# Mainboard_RMII_Interface.net
KiCad netlist of a schematic drawn in Altium Designer
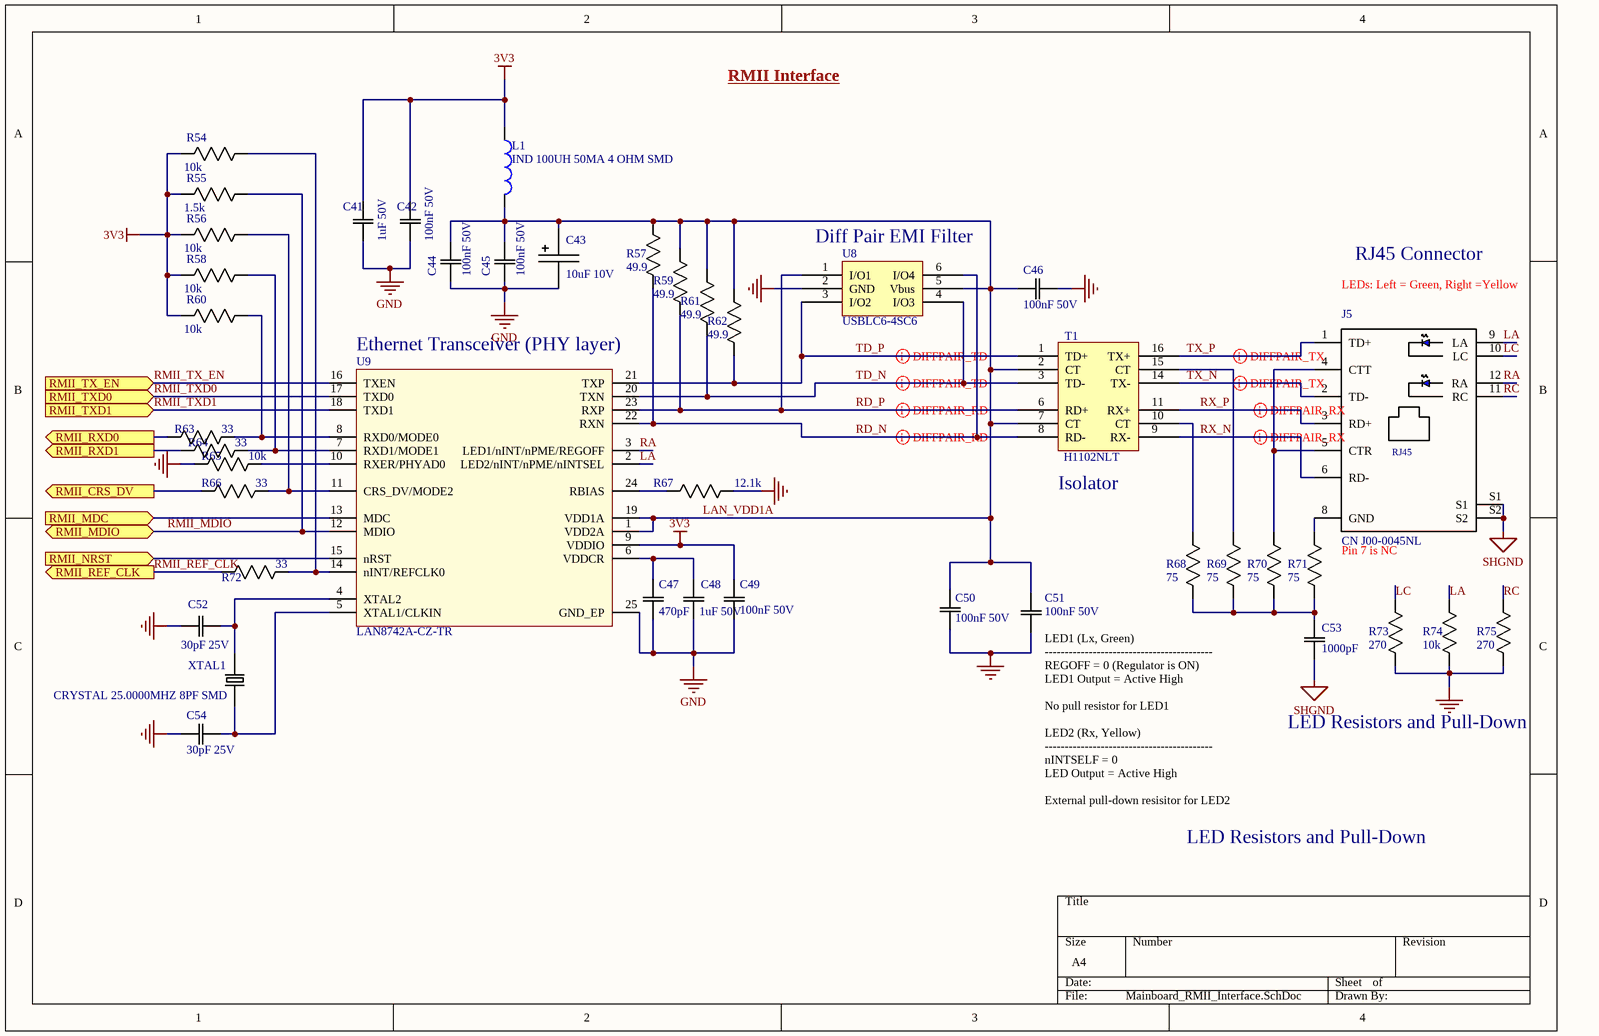
[diagram p0: Mainboard_RMII_Interface.SchDoc]

(export (version "E")
  (design (tool "Eeschema 10.0.6"))
  (components
    (comp (ref "C41")
      (value "1uF 50V")
      (footprint "0805")
      (description "CAP CER 1UF 50V X7R 0805")
      (fields (field (name "TOLERANCE") "10%"))
      (libsource (lib "AltiumLibraries") (part "CAP 1uF 50V"))
    )
    (comp (ref "C42")
      (value "100nF 50V")
      (footprint "0805")
      (description "CAP CER 0.1UF 50V X7R 0805")
      (fields (field (name "TOLERANCE") "10%"))
      (libsource (lib "AltiumLibraries") (part "CAP 100nF 50V"))
    )
    (comp (ref "C43")
      (value "10uF 10V")
      (footprint "1206 Polarized")
      (description "CAP TANT 10UF 10V 1206")
      (fields (field (name "TOLERANCE") "10%"))
      (libsource (lib "AltiumLibraries") (part "CAP TANT 10uF 10V"))
    )
    (comp (ref "C44")
      (value "100nF 50V")
      (footprint "0805")
      (description "CAP CER 0.1UF 50V X7R 0805")
      (fields (field (name "TOLERANCE") "10%"))
      (libsource (lib "AltiumLibraries") (part "CAP 100nF 50V"))
    )
    (comp (ref "C45")
      (value "100nF 50V")
      (footprint "0805")
      (description "CAP CER 0.1UF 50V X7R 0805")
      (fields (field (name "TOLERANCE") "10%"))
      (libsource (lib "AltiumLibraries") (part "CAP 100nF 50V"))
    )
    (comp (ref "C46")
      (value "100nF 50V")
      (footprint "0805")
      (description "CAP CER 0.1UF 50V X7R 0805")
      (fields (field (name "TOLERANCE") "10%"))
      (libsource (lib "AltiumLibraries") (part "CAP 100nF 50V"))
    )
    (comp (ref "C47")
      (value "470pF")
      (footprint "0805")
      (description "CAP CER 470PF 50V X7R 0603/0805")
      (fields (field (name "TOLERANCE") "10%"))
      (libsource (lib "AltiumLibraries") (part "CAP 470pF 50V"))
    )
    (comp (ref "C48")
      (value "1uF 50V")
      (footprint "0805")
      (description "CAP CER 1UF 50V X7R 0805")
      (fields (field (name "TOLERANCE") "10%"))
      (libsource (lib "AltiumLibraries") (part "CAP 1uF 50V"))
    )
    (comp (ref "C49")
      (value "100nF 50V")
      (footprint "0805")
      (description "CAP CER 0.1UF 50V X7R 0805")
      (fields (field (name "TOLERANCE") "10%"))
      (libsource (lib "AltiumLibraries") (part "CAP 100nF 50V"))
    )
    (comp (ref "C50")
      (value "100nF 50V")
      (footprint "0805")
      (description "CAP CER 0.1UF 50V X7R 0805")
      (fields (field (name "TOLERANCE") "10%"))
      (libsource (lib "AltiumLibraries") (part "CAP 100nF 50V"))
    )
    (comp (ref "C51")
      (value "100nF 50V")
      (footprint "0805")
      (description "CAP CER 0.1UF 50V X7R 0805")
      (fields (field (name "TOLERANCE") "10%"))
      (libsource (lib "AltiumLibraries") (part "CAP 100nF 50V"))
    )
    (comp (ref "C52")
      (value "30pF 25V")
      (footprint "0805")
      (description "CAP CER 30PF 25V NP0 0805")
      (fields (field (name "TOLERANCE") "20%"))
      (libsource (lib "AltiumLibraries") (part "CAP 30pF 25V"))
    )
    (comp (ref "C53")
      (value "1000pF")
      (footprint "0805")
      (description "CAP CER 1000PF 50V X7R 0603/0805")
      (fields (field (name "TOLERANCE") "10%"))
      (libsource (lib "AltiumLibraries") (part "CAP 1000pF 50V"))
    )
    (comp (ref "C54")
      (value "30pF 25V")
      (footprint "0805")
      (description "CAP CER 30PF 25V NP0 0805")
      (fields (field (name "TOLERANCE") "20%"))
      (libsource (lib "AltiumLibraries") (part "CAP 30pF 25V"))
    )
    (comp (ref "J5")
      (value "CN J00-0045NL")
      (footprint "RJ45 J00-0045NL")
      (description "CN MAGJACK 1PORT 100 BASE-TX")
      (fields (field (name "MF") "Pulse Electronics") (field (name "MP") "J00-0045NL"))
      (libsource (lib "AltiumLibraries") (part "CN MAGJACK"))
    )
    (comp (ref "L1")
      (value "IND 100UH 50MA 4 OHM SMD")
      (footprint "0805")
      (description "100µH Unshielded Wirewound Inductor 50mA 4Ohm 0805 (2012 Metric)")
      (fields (field (name "MF") "Taiyo Yuden") (field (name "MP") "LBR2012T101K"))
      (libsource (lib "AltiumLibraries") (part "IND 100UH 50MA 4 OHM SMD"))
    )
    (comp (ref "R54")
      (value "10k")
      (footprint "0805")
      (description "RES SMD 10K OHM 1% 1/8W 0805")
      (fields (field (name "TOLERANCE") "1%"))
      (libsource (lib "") (part "RES 10k 1/8W - 1%_1"))
    )
    (comp (ref "R55")
      (value "1.5k")
      (footprint "0805")
      (description "RES SMD 1.5K OHM 1% 1/8W 0805")
      (fields (field (name "TOLERANCE") "1%"))
      (libsource (lib "AltiumLibraries") (part "RES 1.5k 1/8W - 1%"))
    )
    (comp (ref "R56")
      (value "10k")
      (footprint "0805")
      (description "RES SMD 10K OHM 1% 1/8W 0805")
      (fields (field (name "TOLERANCE") "1%"))
      (libsource (lib "AltiumLibraries") (part "RES 10k 1/8W - 1%"))
    )
    (comp (ref "R57")
      (value "49.9")
      (footprint "0805")
      (description "RES SMD 49.9 OHM 1% 1/8W 0805")
      (fields (field (name "TOLERANCE") "1%"))
      (libsource (lib "AltiumLibraries") (part "RES 49.9 1/8W"))
    )
    (comp (ref "R58")
      (value "10k")
      (footprint "0805")
      (description "RES SMD 10K OHM 1% 1/8W 0805")
      (fields (field (name "TOLERANCE") "1%"))
      (libsource (lib "") (part "RES 10k 1/8W - 1%_1"))
    )
    (comp (ref "R59")
      (value "49.9")
      (footprint "0805")
      (description "RES SMD 49.9 OHM 1% 1/8W 0805")
      (fields (field (name "TOLERANCE") "1%"))
      (libsource (lib "AltiumLibraries") (part "RES 49.9 1/8W"))
    )
    (comp (ref "R60")
      (value "10k")
      (footprint "0805")
      (description "RES SMD 10K OHM 1% 1/8W 0805")
      (fields (field (name "TOLERANCE") "1%"))
      (libsource (lib "") (part "RES 10k 1/8W - 1%_1"))
    )
    (comp (ref "R61")
      (value "49.9")
      (footprint "0805")
      (description "RES SMD 49.9 OHM 1% 1/8W 0805")
      (fields (field (name "TOLERANCE") "1%"))
      (libsource (lib "AltiumLibraries") (part "RES 49.9 1/8W"))
    )
    (comp (ref "R62")
      (value "49.9")
      (footprint "0805")
      (description "RES SMD 49.9 OHM 1% 1/8W 0805")
      (fields (field (name "TOLERANCE") "1%"))
      (libsource (lib "AltiumLibraries") (part "RES 49.9 1/8W"))
    )
    (comp (ref "R63")
      (value "33")
      (footprint "0805")
      (description "RES SMD 33 OHM 1% 1/8W 0805")
      (fields (field (name "TOLERANCE") "1%"))
      (libsource (lib "AltiumLibraries") (part "RES 33.0 1/8W - 1%"))
    )
    (comp (ref "R64")
      (value "33")
      (footprint "0805")
      (description "RES SMD 33 OHM 1% 1/8W 0805")
      (fields (field (name "TOLERANCE") "1%"))
      (libsource (lib "AltiumLibraries") (part "RES 33.0 1/8W - 1%"))
    )
    (comp (ref "R65")
      (value "10k")
      (footprint "0805")
      (description "RES SMD 10K OHM 1% 1/8W 0805")
      (fields (field (name "TOLERANCE") "1%"))
      (libsource (lib "AltiumLibraries") (part "RES 10k 1/8W - 1%"))
    )
    (comp (ref "R66")
      (value "33")
      (footprint "0805")
      (description "RES SMD 33 OHM 1% 1/8W 0805")
      (fields (field (name "TOLERANCE") "1%"))
      (libsource (lib "AltiumLibraries") (part "RES 33.0 1/8W - 1%"))
    )
    (comp (ref "R67")
      (value "12.1k")
      (footprint "0805")
      (description "RES SMD 12.1K OHM 1% 1/8W 0805")
      (fields (field (name "TOLERANCE") "1%"))
      (libsource (lib "AltiumLibraries") (part "RES 12.1k 1/8W"))
    )
    (comp (ref "R68")
      (value "75")
      (footprint "0805")
      (description "RES SMD 75 OHM 1% 1/8W 0805")
      (fields (field (name "TOLERANCE") "1%"))
      (libsource (lib "AltiumLibraries") (part "RES 75.0 1/8W - 1%"))
    )
    (comp (ref "R69")
      (value "75")
      (footprint "0805")
      (description "RES SMD 75 OHM 1% 1/8W 0805")
      (fields (field (name "TOLERANCE") "1%"))
      (libsource (lib "AltiumLibraries") (part "RES 75.0 1/8W - 1%"))
    )
    (comp (ref "R70")
      (value "75")
      (footprint "0805")
      (description "RES SMD 75 OHM 1% 1/8W 0805")
      (fields (field (name "TOLERANCE") "1%"))
      (libsource (lib "AltiumLibraries") (part "RES 75.0 1/8W - 1%"))
    )
    (comp (ref "R71")
      (value "75")
      (footprint "0805")
      (description "RES SMD 75 OHM 1% 1/8W 0805")
      (fields (field (name "TOLERANCE") "1%"))
      (libsource (lib "AltiumLibraries") (part "RES 75.0 1/8W - 1%"))
    )
    (comp (ref "R72")
      (value "33")
      (footprint "0805")
      (description "RES SMD 33 OHM 1% 1/8W 0805")
      (fields (field (name "TOLERANCE") "1%"))
      (libsource (lib "AltiumLibraries") (part "RES 33.0 1/8W - 1%"))
    )
    (comp (ref "R73")
      (value "270")
      (footprint "0805")
      (description "RES SMD 270 OHM 5% 1/8W 0805")
      (fields (field (name "TOLERANCE") "5%"))
      (libsource (lib "AltiumLibraries") (part "RES 270.0 1/8W"))
    )
    (comp (ref "R74")
      (value "10k")
      (footprint "0805")
      (description "RES SMD 10K OHM 1% 1/8W 0805")
      (fields (field (name "TOLERANCE") "1%"))
      (libsource (lib "") (part "RES 10k 1/8W - 1%_1"))
    )
    (comp (ref "R75")
      (value "270")
      (footprint "0805")
      (description "RES SMD 270 OHM 5% 1/8W 0805")
      (fields (field (name "TOLERANCE") "5%"))
      (libsource (lib "AltiumLibraries") (part "RES 270.0 1/8W"))
    )
    (comp (ref "T1")
      (value "H1102NLT")
      (footprint "TRANSFORMER")
      (fields (field (name "MF") "Pulse Electronics") (field (name "MP") "H1102NL"))
      (libsource (lib "AltiumLibraries") (part "XFRMR H1102NLT"))
    )
    (comp (ref "U8")
      (value "USBLC6-4SC6")
      (footprint "SOT23-6L")
      (libsource (lib "AltiumLibraries") (part "USBLC6-4SC6"))
    )
    (comp (ref "U9")
      (value "LAN8742A-CZ-TR")
      (footprint "24-QFN (4x4)")
      (fields (field (name "MF") "Microchip Technology"))
      (libsource (lib "AltiumLibraries") (part "LAN8742A-CZ-TR"))
    )
    (comp (ref "XTAL1")
      (value "CRYSTAL 25.0000MHZ 8PF SMD")
      (footprint "SMD-2")
      (description "25MHz ±50ppm Crystal 8pF 70 Ohms 2-SMD, No Lead")
      (fields (field (name "MP") "NX5032GA-25.000000MHZ-LN-CD-1") (field (name "MF") "NDK America, Inc."))
      (libsource (lib "AltiumLibraries") (part "XTAL 25MHZ 8PF SMD"))
    )
  )
  (nets
    (net (code "1") (name "/LA") (class "Default")
      (node (ref "J5") (pin "9") (pinfunction "LA_9") (pintype "passive"))
      (node (ref "R74") (pin "1") (pinfunction "R1_1") (pintype "passive"))
      (node (ref "U9") (pin "2") (pinfunction "LED2/nINT/nPME/nINTSEL_2") (pintype "passive"))
    )
    (net (code "2") (name "/LAN_VDD1A") (class "Default")
      (node (ref "C43") (pin "1") (pinfunction "P$1_1") (pintype "passive"))
      (node (ref "C44") (pin "2") (pinfunction "C2_2") (pintype "passive"))
      (node (ref "C45") (pin "2") (pinfunction "C2_2") (pintype "passive"))
      (node (ref "C46") (pin "1") (pinfunction "C1_1") (pintype "passive"))
      (node (ref "C50") (pin "2") (pinfunction "C2_2") (pintype "passive"))
      (node (ref "C51") (pin "2") (pinfunction "C2_2") (pintype "passive"))
      (node (ref "L1") (pin "2") (pinfunction "2_2") (pintype "passive"))
      (node (ref "R57") (pin "1") (pinfunction "R1_1") (pintype "passive"))
      (node (ref "R59") (pin "1") (pinfunction "R1_1") (pintype "passive"))
      (node (ref "R61") (pin "1") (pinfunction "R1_1") (pintype "passive"))
      (node (ref "R62") (pin "1") (pinfunction "R1_1") (pintype "passive"))
      (node (ref "T1") (pin "2") (pinfunction "CT_2") (pintype "passive"))
      (node (ref "T1") (pin "7") (pinfunction "CT_7") (pintype "passive"))
      (node (ref "U8") (pin "5") (pinfunction "Vbus_5") (pintype "passive"))
      (node (ref "U9") (pin "1") (pinfunction "VDD2A_1") (pintype "passive"))
      (node (ref "U9") (pin "19") (pinfunction "VDD1A_19") (pintype "passive"))
    )
    (net (code "3") (name "/LC") (class "Default")
      (node (ref "J5") (pin "10") (pinfunction "LC_10") (pintype "passive"))
      (node (ref "R73") (pin "1") (pinfunction "R1_1") (pintype "passive"))
    )
    (net (code "4") (name "/RA") (class "Default")
      (node (ref "J5") (pin "12") (pinfunction "RA_12") (pintype "passive"))
      (node (ref "U9") (pin "3") (pinfunction "LED1/nINT/nPME/REGOFF_3") (pintype "passive"))
    )
    (net (code "5") (name "/RC") (class "Default")
      (node (ref "J5") (pin "11") (pinfunction "RC_11") (pintype "passive"))
      (node (ref "R75") (pin "1") (pinfunction "R1_1") (pintype "passive"))
    )
    (net (code "6") (name "/RD_N") (class "Default")
      (node (ref "R57") (pin "2") (pinfunction "R2_2") (pintype "passive"))
      (node (ref "T1") (pin "8") (pinfunction "RD-_8") (pintype "passive"))
      (node (ref "U8") (pin "6") (pinfunction "I/O4_6") (pintype "passive"))
      (node (ref "U9") (pin "22") (pinfunction "RXN_22") (pintype "passive"))
    )
    (net (code "7") (name "/RD_P") (class "Default")
      (node (ref "R59") (pin "2") (pinfunction "R2_2") (pintype "passive"))
      (node (ref "T1") (pin "6") (pinfunction "RD+_6") (pintype "passive"))
      (node (ref "U8") (pin "1") (pinfunction "I/O1_1") (pintype "passive"))
      (node (ref "U9") (pin "23") (pinfunction "RXP_23") (pintype "passive"))
    )
    (net (code "8") (name "/RMII_CRS_DV") (class "Default")
      (node (ref "R66") (pin "2") (pinfunction "R2_2") (pintype "passive"))
    )
    (net (code "9") (name "/RMII_MDC") (class "Default")
      (node (ref "U9") (pin "13") (pinfunction "MDC_13") (pintype "passive"))
    )
    (net (code "10") (name "/RMII_MDIO") (class "Default")
      (node (ref "R55") (pin "1") (pinfunction "R1_1") (pintype "passive"))
      (node (ref "U9") (pin "12") (pinfunction "MDIO_12") (pintype "passive"))
    )
    (net (code "11") (name "/RMII_NRST") (class "Default")
      (node (ref "U9") (pin "15") (pinfunction "nRST_15") (pintype "passive"))
    )
    (net (code "12") (name "/RMII_REF_CLK") (class "Default")
      (node (ref "R72") (pin "2") (pinfunction "R2_2") (pintype "passive"))
    )
    (net (code "13") (name "/RMII_RXD0") (class "Default")
      (node (ref "R63") (pin "2") (pinfunction "R2_2") (pintype "passive"))
    )
    (net (code "14") (name "/RMII_RXD1") (class "Default")
      (node (ref "R64") (pin "2") (pinfunction "R2_2") (pintype "passive"))
    )
    (net (code "15") (name "/RMII_TXD0") (class "Default")
      (node (ref "U9") (pin "17") (pinfunction "TXD0_17") (pintype "passive"))
    )
    (net (code "16") (name "/RMII_TXD1") (class "Default")
      (node (ref "U9") (pin "18") (pinfunction "TXD1_18") (pintype "passive"))
    )
    (net (code "17") (name "/RMII_TX_EN") (class "Default")
      (node (ref "U9") (pin "16") (pinfunction "TXEN_16") (pintype "passive"))
    )
    (net (code "18") (name "/RX_N") (class "Default")
      (node (ref "J5") (pin "6") (pinfunction "RD-_6") (pintype "passive"))
      (node (ref "T1") (pin "9") (pinfunction "RX-_9") (pintype "passive"))
    )
    (net (code "19") (name "/RX_P") (class "Default")
      (node (ref "J5") (pin "3") (pinfunction "RD+_3") (pintype "passive"))
      (node (ref "T1") (pin "11") (pinfunction "RX+_11") (pintype "passive"))
    )
    (net (code "20") (name "/TD_N") (class "Default")
      (node (ref "R61") (pin "2") (pinfunction "R2_2") (pintype "passive"))
      (node (ref "T1") (pin "3") (pinfunction "TD-_3") (pintype "passive"))
      (node (ref "U8") (pin "4") (pinfunction "I/O3_4") (pintype "passive"))
      (node (ref "U9") (pin "20") (pinfunction "TXN_20") (pintype "passive"))
    )
    (net (code "21") (name "/TD_P") (class "Default")
      (node (ref "R62") (pin "2") (pinfunction "R2_2") (pintype "passive"))
      (node (ref "T1") (pin "1") (pinfunction "TD+_1") (pintype "passive"))
      (node (ref "U8") (pin "3") (pinfunction "I/O2_3") (pintype "passive"))
      (node (ref "U9") (pin "21") (pinfunction "TXP_21") (pintype "passive"))
    )
    (net (code "22") (name "/TX_N") (class "Default")
      (node (ref "J5") (pin "2") (pinfunction "TD-_2") (pintype "passive"))
      (node (ref "T1") (pin "14") (pinfunction "TX-_14") (pintype "passive"))
    )
    (net (code "23") (name "/TX_P") (class "Default")
      (node (ref "J5") (pin "1") (pinfunction "TD+_1") (pintype "passive"))
      (node (ref "T1") (pin "16") (pinfunction "TX+_16") (pintype "passive"))
    )
    (net (code "24") (name "3V3") (class "Default")
      (node (ref "C41") (pin "2") (pinfunction "C2_2") (pintype "passive"))
      (node (ref "C42") (pin "2") (pinfunction "C2_2") (pintype "passive"))
      (node (ref "C49") (pin "2") (pinfunction "C2_2") (pintype "passive"))
      (node (ref "L1") (pin "1") (pinfunction "1_1") (pintype "passive"))
      (node (ref "R54") (pin "2") (pinfunction "R2_2") (pintype "passive"))
      (node (ref "R55") (pin "2") (pinfunction "R2_2") (pintype "passive"))
      (node (ref "R56") (pin "2") (pinfunction "R2_2") (pintype "passive"))
      (node (ref "R58") (pin "2") (pinfunction "R2_2") (pintype "passive"))
      (node (ref "R60") (pin "2") (pinfunction "R2_2") (pintype "passive"))
      (node (ref "U9") (pin "9") (pinfunction "VDDIO_9") (pintype "passive"))
    )
    (net (code "25") (name "GND") (class "Default")
      (node (ref "C41") (pin "1") (pinfunction "C1_1") (pintype "passive"))
      (node (ref "C42") (pin "1") (pinfunction "C1_1") (pintype "passive"))
      (node (ref "C43") (pin "2") (pinfunction "P$2_2") (pintype "passive"))
      (node (ref "C44") (pin "1") (pinfunction "C1_1") (pintype "passive"))
      (node (ref "C45") (pin "1") (pinfunction "C1_1") (pintype "passive"))
      (node (ref "C46") (pin "2") (pinfunction "C2_2") (pintype "passive"))
      (node (ref "C47") (pin "1") (pinfunction "C1_1") (pintype "passive"))
      (node (ref "C48") (pin "1") (pinfunction "C1_1") (pintype "passive"))
      (node (ref "C49") (pin "1") (pinfunction "C1_1") (pintype "passive"))
      (node (ref "C50") (pin "1") (pinfunction "C1_1") (pintype "passive"))
      (node (ref "C51") (pin "1") (pinfunction "C1_1") (pintype "passive"))
      (node (ref "C52") (pin "1") (pinfunction "C1_1") (pintype "passive"))
      (node (ref "C54") (pin "1") (pinfunction "C1_1") (pintype "passive"))
      (node (ref "R65") (pin "2") (pinfunction "R2_2") (pintype "passive"))
      (node (ref "R67") (pin "1") (pinfunction "R1_1") (pintype "passive"))
      (node (ref "R73") (pin "2") (pinfunction "R2_2") (pintype "passive"))
      (node (ref "R74") (pin "2") (pinfunction "R2_2") (pintype "passive"))
      (node (ref "R75") (pin "2") (pinfunction "R2_2") (pintype "passive"))
      (node (ref "U8") (pin "2") (pinfunction "GND_2") (pintype "passive"))
      (node (ref "U9") (pin "25") (pinfunction "GND_EP_25") (pintype "passive"))
    )
    (net (code "26") (name "Net-(C47-C2)") (class "Default")
      (node (ref "C47") (pin "2") (pinfunction "C2_2") (pintype "passive"))
      (node (ref "C48") (pin "2") (pinfunction "C2_2") (pintype "passive"))
      (node (ref "U9") (pin "6") (pinfunction "VDDCR_6") (pintype "passive"))
    )
    (net (code "27") (name "Net-(C52-C2)") (class "Default")
      (node (ref "C52") (pin "2") (pinfunction "C2_2") (pintype "passive"))
      (node (ref "U9") (pin "4") (pinfunction "XTAL2_4") (pintype "passive"))
      (node (ref "XTAL1") (pin "2") (pinfunction "2_2") (pintype "passive"))
    )
    (net (code "28") (name "Net-(C53-C2)") (class "Default")
      (node (ref "C53") (pin "2") (pinfunction "C2_2") (pintype "passive"))
      (node (ref "R68") (pin "2") (pinfunction "R2_2") (pintype "passive"))
      (node (ref "R69") (pin "2") (pinfunction "R2_2") (pintype "passive"))
      (node (ref "R70") (pin "2") (pinfunction "R2_2") (pintype "passive"))
      (node (ref "R71") (pin "2") (pinfunction "R2_2") (pintype "passive"))
    )
    (net (code "29") (name "Net-(C54-C2)") (class "Default")
      (node (ref "C54") (pin "2") (pinfunction "C2_2") (pintype "passive"))
      (node (ref "U9") (pin "5") (pinfunction "XTAL1/CLKIN_5") (pintype "passive"))
      (node (ref "XTAL1") (pin "1") (pinfunction "1_1") (pintype "passive"))
    )
    (net (code "30") (name "Net-(J5-CTR)") (class "Default")
      (node (ref "J5") (pin "4") (pinfunction "CTT_4") (pintype "passive"))
      (node (ref "J5") (pin "5") (pinfunction "CTR_5") (pintype "passive"))
      (node (ref "R70") (pin "1") (pinfunction "R1_1") (pintype "passive"))
    )
    (net (code "31") (name "Net-(J5-GND)") (class "Default")
      (node (ref "J5") (pin "8") (pinfunction "GND_8") (pintype "passive"))
      (node (ref "R71") (pin "1") (pinfunction "R1_1") (pintype "passive"))
    )
    (net (code "32") (name "Net-(R54-R1)") (class "Default")
      (node (ref "R54") (pin "1") (pinfunction "R1_1") (pintype "passive"))
      (node (ref "R72") (pin "1") (pinfunction "R1_1") (pintype "passive"))
      (node (ref "U9") (pin "14") (pinfunction "nINT/REFCLK0_14") (pintype "passive"))
    )
    (net (code "33") (name "Net-(R56-R1)") (class "Default")
      (node (ref "R56") (pin "1") (pinfunction "R1_1") (pintype "passive"))
      (node (ref "R66") (pin "1") (pinfunction "R1_1") (pintype "passive"))
      (node (ref "U9") (pin "11") (pinfunction "CRS_DV/MODE2_11") (pintype "passive"))
    )
    (net (code "34") (name "Net-(R58-R1)") (class "Default")
      (node (ref "R58") (pin "1") (pinfunction "R1_1") (pintype "passive"))
      (node (ref "R64") (pin "1") (pinfunction "R1_1") (pintype "passive"))
      (node (ref "U9") (pin "7") (pinfunction "RXD1/MODE1_7") (pintype "passive"))
    )
    (net (code "35") (name "Net-(R60-R1)") (class "Default")
      (node (ref "R60") (pin "1") (pinfunction "R1_1") (pintype "passive"))
      (node (ref "R63") (pin "1") (pinfunction "R1_1") (pintype "passive"))
      (node (ref "U9") (pin "8") (pinfunction "RXD0/MODE0_8") (pintype "passive"))
    )
    (net (code "36") (name "Net-(R65-R1)") (class "Default")
      (node (ref "R65") (pin "1") (pinfunction "R1_1") (pintype "passive"))
      (node (ref "U9") (pin "10") (pinfunction "RXER/PHYAD0_10") (pintype "passive"))
    )
    (net (code "37") (name "Net-(R67-R2)") (class "Default")
      (node (ref "R67") (pin "2") (pinfunction "R2_2") (pintype "passive"))
      (node (ref "U9") (pin "24") (pinfunction "RBIAS_24") (pintype "passive"))
    )
    (net (code "38") (name "Net-(R68-R1)") (class "Default")
      (node (ref "R68") (pin "1") (pinfunction "R1_1") (pintype "passive"))
      (node (ref "T1") (pin "10") (pinfunction "CT_10") (pintype "passive"))
    )
    (net (code "39") (name "Net-(R69-R1)") (class "Default")
      (node (ref "R69") (pin "1") (pinfunction "R1_1") (pintype "passive"))
      (node (ref "T1") (pin "15") (pinfunction "CT_15") (pintype "passive"))
    )
    (net (code "40") (name "SHGND") (class "Default")
      (node (ref "C53") (pin "1") (pinfunction "C1_1") (pintype "passive"))
      (node (ref "J5") (pin "S1") (pinfunction "S1_S1") (pintype "passive"))
      (node (ref "J5") (pin "S2") (pinfunction "S2_S2") (pintype "passive"))
    )
  )
)
